# SNES_TST_Sheet1.net
KiCad netlist of a schematic drawn in Altium Designer
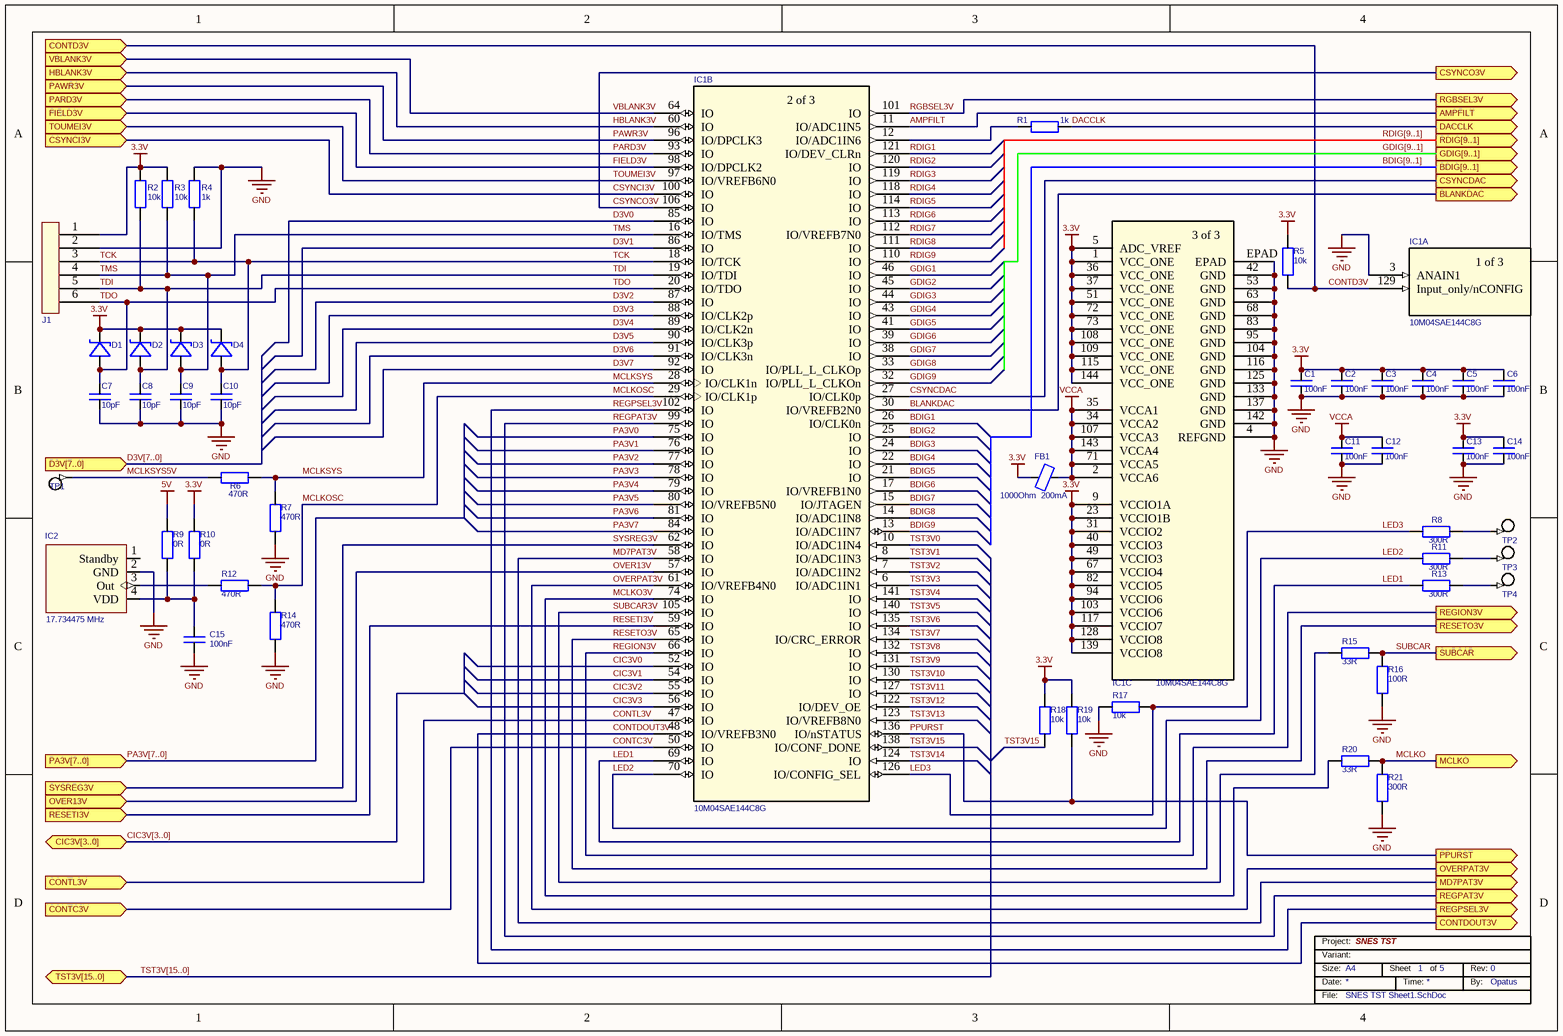
[diagram p0: SNES TST Sheet1.SchDoc]

(export (version "E")
  (design (tool "Eeschema 10.0.6"))
  (components
    (comp (ref "C1")
      (value "100nF")
      (footprint "Cap_0402_Chip")
      (fields
        (field (name "TOLERANCE") "±20%")
        (field (name "Comment") "Ceramic Capacitor 100nF 10V ±20% X7R 0402")
      )
      (libsource (lib "PCB") (part "Capacitor"))
    )
    (comp (ref "C2")
      (value "100nF")
      (footprint "Cap_0402_Chip")
      (fields
        (field (name "TOLERANCE") "±20%")
        (field (name "Comment") "Ceramic Capacitor 100nF 10V ±20% X7R 0402")
      )
      (libsource (lib "PCB") (part "Capacitor"))
    )
    (comp (ref "C3")
      (value "100nF")
      (footprint "Cap_0402_Chip")
      (fields
        (field (name "TOLERANCE") "±20%")
        (field (name "Comment") "Ceramic Capacitor 100nF 10V ±20% X7R 0402")
      )
      (libsource (lib "PCB") (part "Capacitor"))
    )
    (comp (ref "C4")
      (value "100nF")
      (footprint "Cap_0402_Chip")
      (fields
        (field (name "TOLERANCE") "±20%")
        (field (name "Comment") "Ceramic Capacitor 100nF 10V ±20% X7R 0402")
      )
      (libsource (lib "PCB") (part "Capacitor"))
    )
    (comp (ref "C5")
      (value "100nF")
      (footprint "Cap_0402_Chip")
      (fields
        (field (name "TOLERANCE") "±20%")
        (field (name "Comment") "Ceramic Capacitor 100nF 10V ±20% X7R 0402")
      )
      (libsource (lib "PCB") (part "Capacitor"))
    )
    (comp (ref "C6")
      (value "100nF")
      (footprint "Cap_0402_Chip")
      (fields
        (field (name "TOLERANCE") "±20%")
        (field (name "Comment") "Ceramic Capacitor 100nF 10V ±20% X7R 0402")
      )
      (libsource (lib "PCB") (part "Capacitor"))
    )
    (comp (ref "C7")
      (value "10pF")
      (footprint "Cap_0402_Chip")
      (fields
        (field (name "TOLERANCE") "±20%")
        (field (name "Comment") "Ceramic Capacitor 10pF 10V ±20% X7R 0402")
      )
      (libsource (lib "PCB") (part "Capacitor"))
    )
    (comp (ref "C8")
      (value "10pF")
      (footprint "Cap_0402_Chip")
      (fields
        (field (name "TOLERANCE") "±20%")
        (field (name "Comment") "Ceramic Capacitor 10pF 10V ±20% X7R 0402")
      )
      (libsource (lib "PCB") (part "Capacitor"))
    )
    (comp (ref "C9")
      (value "10pF")
      (footprint "Cap_0402_Chip")
      (fields
        (field (name "TOLERANCE") "±20%")
        (field (name "Comment") "Ceramic Capacitor 10pF 10V ±20% X7R 0402")
      )
      (libsource (lib "PCB") (part "Capacitor"))
    )
    (comp (ref "C10")
      (value "10pF")
      (footprint "Cap_0402_Chip")
      (fields
        (field (name "TOLERANCE") "±20%")
        (field (name "Comment") "Ceramic Capacitor 10pF 10V ±20% X7R 0402")
      )
      (libsource (lib "PCB") (part "Capacitor"))
    )
    (comp (ref "C11")
      (value "100nF")
      (footprint "Cap_0402_Chip")
      (fields
        (field (name "TOLERANCE") "±20%")
        (field (name "Comment") "Ceramic Capacitor 100nF 10V ±20% X7R 0402")
      )
      (libsource (lib "PCB") (part "Capacitor"))
    )
    (comp (ref "C12")
      (value "100nF")
      (footprint "Cap_0402_Chip")
      (fields
        (field (name "TOLERANCE") "±20%")
        (field (name "Comment") "Ceramic Capacitor 100nF 10V ±20% X7R 0402")
      )
      (libsource (lib "PCB") (part "Capacitor"))
    )
    (comp (ref "C13")
      (value "100nF")
      (footprint "Cap_0402_Chip")
      (fields
        (field (name "TOLERANCE") "±20%")
        (field (name "Comment") "Ceramic Capacitor 100nF 10V ±20% X7R 0402")
      )
      (libsource (lib "PCB") (part "Capacitor"))
    )
    (comp (ref "C14")
      (value "100nF")
      (footprint "Cap_0402_Chip")
      (fields
        (field (name "TOLERANCE") "±20%")
        (field (name "Comment") "Ceramic Capacitor 100nF 10V ±20% X7R 0402")
      )
      (libsource (lib "PCB") (part "Capacitor"))
    )
    (comp (ref "C15")
      (value "100nF")
      (footprint "Cap_0402_Chip")
      (fields
        (field (name "TOLERANCE") "±20%")
        (field (name "Comment") "Ceramic Capacitor 100nF 10V ±20% X7R 0402")
      )
      (libsource (lib "PCB") (part "Capacitor"))
    )
    (comp (ref "D1")
      (value "BAT54WS")
      (footprint "SOD323")
      (description "Schottky Diode")
      (fields (field (name "MANUFACTURER_PART_NUMBER") "BAT54WS-7-F"))
      (libsource (lib "PCB") (part "Schottky Diode"))
    )
    (comp (ref "D2")
      (value "BAT54WS")
      (footprint "SOD323")
      (description "Schottky Diode")
      (fields (field (name "MANUFACTURER_PART_NUMBER") "BAT54WS-7-F"))
      (libsource (lib "PCB") (part "Schottky Diode"))
    )
    (comp (ref "D3")
      (value "BAT54WS")
      (footprint "SOD323")
      (description "Schottky Diode")
      (fields (field (name "MANUFACTURER_PART_NUMBER") "BAT54WS-7-F"))
      (libsource (lib "PCB") (part "Schottky Diode"))
    )
    (comp (ref "D4")
      (value "BAT54WS")
      (footprint "SOD323")
      (description "Schottky Diode")
      (fields (field (name "MANUFACTURER_PART_NUMBER") "BAT54WS-7-F"))
      (libsource (lib "PCB") (part "Schottky Diode"))
    )
    (comp (ref "FB1")
      (value "1000Ohm  200mA")
      (footprint "Ind_0402_Chip")
      (fields (field (name "MANUFACTURER_PART_NUMBER") "MMZ1005S102CT000"))
      (libsource (lib "PCB") (part "Ferrite Bead"))
    )
    (comp (ref "IC1")
      (value "10M04SAE144C8G")
      (footprint "EQFP-144_A:1P65_")
      (description "No Description Available")
      (fields (field (name "COPYRIGHT") "Copyright (C) 2018 Accelerated Designs. All rights reserved"))
      (libsource (lib "") (part "10M08SAE144C8G_1"))
    )
    (comp (ref "IC2")
      (value "17.734475 MHz")
      (footprint "Quarz 7.5mm")
      (description "Oscillator")
      (fields
        (field (name "FREQUENCY") "17.734475 MHz")
        (field (name "MANUFACTURER_PART_NUMBER") "LFSPXO020648Bulk")
      )
      (libsource (lib "PCB") (part "Oscillator"))
    )
    (comp (ref "J1")
      (value "Conn 6P")
      (footprint "Con6P")
      (description "6 Pole Connector")
      (libsource (lib "PCB") (part "Conn 6P"))
    )
    (comp (ref "R1")
      (value "1k")
      (footprint "Res_0402_Chip")
      (fields (field (name "TOLERANCE") "±1%") (field (name "Comment") "Resistor 1k 0402 ±1%"))
      (libsource (lib "") (part "R_1"))
    )
    (comp (ref "R2")
      (value "10k")
      (footprint "Res_0402_Chip")
      (fields (field (name "TOLERANCE") "±1%") (field (name "Comment") "Resistor 10k 0402 ±1%"))
      (libsource (lib "") (part "R_2"))
    )
    (comp (ref "R3")
      (value "10k")
      (footprint "Res_0402_Chip")
      (fields (field (name "TOLERANCE") "±1%") (field (name "Comment") "Resistor 10k 0402 ±1%"))
      (libsource (lib "") (part "R_2"))
    )
    (comp (ref "R4")
      (value "1k")
      (footprint "Res_0402_Chip")
      (fields (field (name "TOLERANCE") "±1%") (field (name "Comment") "Resistor 1k 0402 ±1%"))
      (libsource (lib "") (part "R_3"))
    )
    (comp (ref "R5")
      (value "10k")
      (footprint "Res_0402_Chip")
      (fields (field (name "TOLERANCE") "±1%") (field (name "Comment") "Resistor 10k 0402 ±1%"))
      (libsource (lib "") (part "R_2"))
    )
    (comp (ref "R6")
      (value "470R")
      (footprint "Res_0603_Chip")
      (fields (field (name "TOLERANCE") "±1%") (field (name "Comment") "Resistor 470R 0603 ±1%"))
      (libsource (lib "PCB") (part "R"))
    )
    (comp (ref "R7")
      (value "470R")
      (footprint "Res_0603_Chip")
      (fields (field (name "TOLERANCE") "±1%") (field (name "Comment") "Resistor 470R 0603 ±1%"))
      (libsource (lib "") (part "R_2"))
    )
    (comp (ref "R8")
      (value "300R")
      (footprint "Res_0603_Chip")
      (fields (field (name "TOLERANCE") "±1%") (field (name "Comment") "Resistor 300R 0603 ±1%"))
      (libsource (lib "PCB") (part "R"))
    )
    (comp (ref "R9")
      (value "0R")
      (footprint "Res_0402_Chip")
      (fields (field (name "Comment") "Resistor 0R 0402 "))
      (libsource (lib "") (part "R_2"))
    )
    (comp (ref "R10")
      (value "0R")
      (footprint "Res_0402_Chip")
      (fields (field (name "Comment") "Resistor 0R 0402 "))
      (libsource (lib "") (part "R_2"))
    )
    (comp (ref "R11")
      (value "300R")
      (footprint "Res_0603_Chip")
      (fields (field (name "TOLERANCE") "±1%") (field (name "Comment") "Resistor 300R 0603 ±1%"))
      (libsource (lib "PCB") (part "R"))
    )
    (comp (ref "R12")
      (value "470R")
      (footprint "Res_0603_Chip")
      (fields (field (name "TOLERANCE") "±1%") (field (name "Comment") "Resistor 470R 0603 ±1%"))
      (libsource (lib "PCB") (part "R"))
    )
    (comp (ref "R13")
      (value "300R")
      (footprint "Res_0603_Chip")
      (fields (field (name "TOLERANCE") "±1%") (field (name "Comment") "Resistor 300R 0603 ±1%"))
      (libsource (lib "PCB") (part "R"))
    )
    (comp (ref "R14")
      (value "470R")
      (footprint "Res_0603_Chip")
      (fields (field (name "TOLERANCE") "±1%") (field (name "Comment") "Resistor 470R 0603 ±1%"))
      (libsource (lib "") (part "R_2"))
    )
    (comp (ref "R15")
      (value "33R")
      (footprint "Res_0603_Chip")
      (fields (field (name "TOLERANCE") "±1%") (field (name "Comment") "Resistor 33R 0603 ±1%"))
      (libsource (lib "PCB") (part "R"))
    )
    (comp (ref "R16")
      (value "100R")
      (footprint "Res_0603_Chip")
      (fields (field (name "TOLERANCE") "±1%") (field (name "Comment") "Resistor 100R 0603 ±1%"))
      (libsource (lib "") (part "R_2"))
    )
    (comp (ref "R17")
      (value "10k")
      (footprint "Res_0402_Chip")
      (fields (field (name "TOLERANCE") "±1%") (field (name "Comment") "Resistor 10k 0402 ±1%"))
      (libsource (lib "") (part "R_1"))
    )
    (comp (ref "R18")
      (value "10k")
      (footprint "Res_0402_Chip")
      (fields (field (name "TOLERANCE") "±1%") (field (name "Comment") "Resistor 10k 0402 ±1%"))
      (libsource (lib "") (part "R_2"))
    )
    (comp (ref "R19")
      (value "10k")
      (footprint "Res_0402_Chip")
      (fields (field (name "TOLERANCE") "±1%") (field (name "Comment") "Resistor 10k 0402 ±1%"))
      (libsource (lib "") (part "R_2"))
    )
    (comp (ref "R20")
      (value "33R")
      (footprint "Res_0603_Chip")
      (fields (field (name "TOLERANCE") "±1%") (field (name "Comment") "Resistor 33R 0603 ±1%"))
      (libsource (lib "PCB") (part "R"))
    )
    (comp (ref "R21")
      (value "300R")
      (footprint "Res_0603_Chip")
      (fields (field (name "TOLERANCE") "±1%") (field (name "Comment") "Resistor 300R 0603 ±1%"))
      (libsource (lib "") (part "R_2"))
    )
    (comp (ref "TP1")
      (value "Pin Connector")
      (footprint "Pin Connector Small")
      (libsource (lib "PCB") (part "Pin Connector"))
    )
    (comp (ref "TP2")
      (value "Pin Connector")
      (footprint "Pin Connector Small")
      (libsource (lib "PCB") (part "Pin Connector"))
    )
    (comp (ref "TP3")
      (value "Pin Connector")
      (footprint "Pin Connector Small")
      (libsource (lib "PCB") (part "Pin Connector"))
    )
    (comp (ref "TP4")
      (value "Pin Connector")
      (footprint "Pin Connector Small")
      (libsource (lib "PCB") (part "Pin Connector"))
    )
  )
  (nets
    (net (code "1") (name "/AMPFILT") (class "Default")
      (node (ref "IC1") (pin "11") (pinfunction "IO/ADC1IN5_11") (pintype "output"))
    )
    (net (code "2") (name "/BDIG1") (class "Default")
      (node (ref "IC1") (pin "26") (pinfunction "IO/CLK0n_26") (pintype "output"))
    )
    (net (code "3") (name "/BDIG2") (class "Default")
      (node (ref "IC1") (pin "25") (pinfunction "IO_25") (pintype "output"))
    )
    (net (code "4") (name "/BDIG3") (class "Default")
      (node (ref "IC1") (pin "24") (pinfunction "IO_24") (pintype "output"))
    )
    (net (code "5") (name "/BDIG4") (class "Default")
      (node (ref "IC1") (pin "22") (pinfunction "IO_22") (pintype "output"))
    )
    (net (code "6") (name "/BDIG5") (class "Default")
      (node (ref "IC1") (pin "21") (pinfunction "IO_21") (pintype "output"))
    )
    (net (code "7") (name "/BDIG6") (class "Default")
      (node (ref "IC1") (pin "17") (pinfunction "IO/VREFB1N0_17") (pintype "output"))
    )
    (net (code "8") (name "/BDIG7") (class "Default")
      (node (ref "IC1") (pin "15") (pinfunction "IO/JTAGEN_15") (pintype "output"))
    )
    (net (code "9") (name "/BDIG8") (class "Default")
      (node (ref "IC1") (pin "14") (pinfunction "IO/ADC1IN8_14") (pintype "output"))
    )
    (net (code "10") (name "/BDIG9") (class "Default")
      (node (ref "IC1") (pin "13") (pinfunction "IO/ADC1IN7_13") (pintype "bidirectional"))
    )
    (net (code "12") (name "/BLANKDAC") (class "Default")
      (node (ref "IC1") (pin "30") (pinfunction "IO/VREFB2N0_30") (pintype "output"))
    )
    (net (code "13") (name "/CIC3V0") (class "Default")
      (node (ref "IC1") (pin "52") (pinfunction "IO_52") (pintype "bidirectional"))
    )
    (net (code "14") (name "/CIC3V1") (class "Default")
      (node (ref "IC1") (pin "54") (pinfunction "IO_54") (pintype "bidirectional"))
    )
    (net (code "15") (name "/CIC3V2") (class "Default")
      (node (ref "IC1") (pin "55") (pinfunction "IO_55") (pintype "bidirectional"))
    )
    (net (code "16") (name "/CIC3V3") (class "Default")
      (node (ref "IC1") (pin "56") (pinfunction "IO_56") (pintype "bidirectional"))
    )
    (net (code "18") (name "/CONTC3V") (class "Default")
      (node (ref "IC1") (pin "50") (pinfunction "IO_50") (pintype "bidirectional"))
    )
    (net (code "19") (name "/CONTD3V") (class "Default")
      (node (ref "IC1") (pin "129") (pinfunction "Input_only/nCONFIG_129") (pintype "input"))
      (node (ref "R5") (pin "2") (pintype "passive"))
    )
    (net (code "20") (name "/CONTDOUT3V") (class "Default")
      (node (ref "IC1") (pin "48") (pinfunction "IO/VREFB3N0_48") (pintype "bidirectional"))
    )
    (net (code "21") (name "/CONTL3V") (class "Default")
      (node (ref "IC1") (pin "47") (pinfunction "IO_47") (pintype "bidirectional"))
    )
    (net (code "22") (name "/CSYNCDAC") (class "Default")
      (node (ref "IC1") (pin "27") (pinfunction "IO/CLK0p_27") (pintype "output"))
    )
    (net (code "23") (name "/CSYNCI3V") (class "Default")
      (node (ref "IC1") (pin "100") (pinfunction "IO_100") (pintype "bidirectional"))
    )
    (net (code "24") (name "/CSYNCO3V") (class "Default")
      (node (ref "IC1") (pin "106") (pinfunction "IO_106") (pintype "bidirectional"))
    )
    (net (code "25") (name "/D3V0") (class "Default")
      (node (ref "IC1") (pin "85") (pinfunction "IO_85") (pintype "bidirectional"))
    )
    (net (code "26") (name "/D3V1") (class "Default")
      (node (ref "IC1") (pin "86") (pinfunction "IO_86") (pintype "bidirectional"))
    )
    (net (code "27") (name "/D3V2") (class "Default")
      (node (ref "IC1") (pin "87") (pinfunction "IO_87") (pintype "bidirectional"))
    )
    (net (code "28") (name "/D3V3") (class "Default")
      (node (ref "IC1") (pin "88") (pinfunction "IO/CLK2p_88") (pintype "bidirectional"))
    )
    (net (code "29") (name "/D3V4") (class "Default")
      (node (ref "IC1") (pin "89") (pinfunction "IO/CLK2n_89") (pintype "bidirectional"))
    )
    (net (code "30") (name "/D3V5") (class "Default")
      (node (ref "IC1") (pin "90") (pinfunction "IO/CLK3p_90") (pintype "bidirectional"))
    )
    (net (code "31") (name "/D3V6") (class "Default")
      (node (ref "IC1") (pin "91") (pinfunction "IO/CLK3n_91") (pintype "bidirectional"))
    )
    (net (code "32") (name "/D3V7") (class "Default")
      (node (ref "IC1") (pin "92") (pinfunction "IO_92") (pintype "bidirectional"))
    )
    (net (code "34") (name "/DACCLK") (class "Default") (node (ref "R1") (pin "2") (pintype "passive")))
    (net (code "35") (name "/FIELD3V") (class "Default")
      (node (ref "IC1") (pin "98") (pinfunction "IO/DPCLK2_98") (pintype "bidirectional"))
    )
    (net (code "36") (name "/GDIG1") (class "Default")
      (node (ref "IC1") (pin "46") (pinfunction "IO_46") (pintype "output"))
    )
    (net (code "37") (name "/GDIG2") (class "Default")
      (node (ref "IC1") (pin "45") (pinfunction "IO_45") (pintype "output"))
    )
    (net (code "38") (name "/GDIG3") (class "Default")
      (node (ref "IC1") (pin "44") (pinfunction "IO_44") (pintype "output"))
    )
    (net (code "39") (name "/GDIG4") (class "Default")
      (node (ref "IC1") (pin "43") (pinfunction "IO_43") (pintype "output"))
    )
    (net (code "40") (name "/GDIG5") (class "Default")
      (node (ref "IC1") (pin "41") (pinfunction "IO_41") (pintype "output"))
    )
    (net (code "41") (name "/GDIG6") (class "Default")
      (node (ref "IC1") (pin "39") (pinfunction "IO_39") (pintype "output"))
    )
    (net (code "42") (name "/GDIG7") (class "Default")
      (node (ref "IC1") (pin "38") (pinfunction "IO_38") (pintype "output"))
    )
    (net (code "43") (name "/GDIG8") (class "Default")
      (node (ref "IC1") (pin "33") (pinfunction "IO/PLL_L_CLKOp_33") (pintype "output"))
    )
    (net (code "44") (name "/GDIG9") (class "Default")
      (node (ref "IC1") (pin "32") (pinfunction "IO/PLL_L_CLKOn_32") (pintype "output"))
    )
    (net (code "46") (name "/HBLANK3V") (class "Default")
      (node (ref "IC1") (pin "60") (pinfunction "IO_60") (pintype "bidirectional"))
    )
    (net (code "47") (name "/LED1") (class "Default")
      (node (ref "IC1") (pin "69") (pinfunction "IO_69") (pintype "bidirectional"))
      (node (ref "R13") (pin "2") (pintype "passive"))
    )
    (net (code "48") (name "/LED2") (class "Default")
      (node (ref "IC1") (pin "70") (pinfunction "IO_70") (pintype "bidirectional"))
      (node (ref "R11") (pin "2") (pintype "passive"))
    )
    (net (code "49") (name "/LED3") (class "Default")
      (node (ref "IC1") (pin "126") (pinfunction "IO/CONFIG_SEL_126") (pintype "bidirectional"))
      (node (ref "R17") (pin "2") (pintype "passive"))
      (node (ref "R8") (pin "2") (pintype "passive"))
    )
    (net (code "50") (name "/MCLKO") (class "Default")
      (node (ref "R20") (pin "1") (pintype "passive"))
      (node (ref "R21") (pin "1") (pintype "passive"))
    )
    (net (code "51") (name "/MCLKO3V") (class "Default")
      (node (ref "IC1") (pin "74") (pinfunction "IO_74") (pintype "bidirectional"))
      (node (ref "R20") (pin "2") (pintype "passive"))
    )
    (net (code "52") (name "/MCLKOSC") (class "Default")
      (node (ref "IC1") (pin "29") (pinfunction "IO/CLK1p_29") (pintype "bidirectional"))
      (node (ref "R12") (pin "1") (pintype "passive"))
      (node (ref "R14") (pin "1") (pintype "passive"))
    )
    (net (code "53") (name "/MCLKSYS") (class "Default")
      (node (ref "IC1") (pin "28") (pinfunction "IO/CLK1n_28") (pintype "bidirectional"))
      (node (ref "R6") (pin "1") (pintype "passive"))
      (node (ref "R7") (pin "1") (pintype "passive"))
    )
    (net (code "54") (name "/MCLKSYS5V") (class "Default")
      (node (ref "R6") (pin "2") (pintype "passive"))
      (node (ref "TP1") (pin "1") (pinfunction "0_1") (pintype "output"))
    )
    (net (code "55") (name "/MD7PAT3V") (class "Default")
      (node (ref "IC1") (pin "58") (pinfunction "IO_58") (pintype "bidirectional"))
    )
    (net (code "56") (name "/OVER13V") (class "Default")
      (node (ref "IC1") (pin "57") (pinfunction "IO_57") (pintype "bidirectional"))
    )
    (net (code "57") (name "/OVERPAT3V") (class "Default")
      (node (ref "IC1") (pin "61") (pinfunction "IO/VREFB4N0_61") (pintype "bidirectional"))
    )
    (net (code "58") (name "/PA3V0") (class "Default")
      (node (ref "IC1") (pin "75") (pinfunction "IO_75") (pintype "bidirectional"))
    )
    (net (code "59") (name "/PA3V1") (class "Default")
      (node (ref "IC1") (pin "76") (pinfunction "IO_76") (pintype "bidirectional"))
    )
    (net (code "60") (name "/PA3V2") (class "Default")
      (node (ref "IC1") (pin "77") (pinfunction "IO_77") (pintype "bidirectional"))
    )
    (net (code "61") (name "/PA3V3") (class "Default")
      (node (ref "IC1") (pin "78") (pinfunction "IO_78") (pintype "bidirectional"))
    )
    (net (code "62") (name "/PA3V4") (class "Default")
      (node (ref "IC1") (pin "79") (pinfunction "IO_79") (pintype "bidirectional"))
    )
    (net (code "63") (name "/PA3V5") (class "Default")
      (node (ref "IC1") (pin "80") (pinfunction "IO/VREFB5N0_80") (pintype "bidirectional"))
    )
    (net (code "64") (name "/PA3V6") (class "Default")
      (node (ref "IC1") (pin "81") (pinfunction "IO_81") (pintype "bidirectional"))
    )
    (net (code "65") (name "/PA3V7") (class "Default")
      (node (ref "IC1") (pin "84") (pinfunction "IO_84") (pintype "bidirectional"))
    )
    (net (code "67") (name "/PARD3V") (class "Default")
      (node (ref "IC1") (pin "93") (pinfunction "IO_93") (pintype "bidirectional"))
    )
    (net (code "68") (name "/PAWR3V") (class "Default")
      (node (ref "IC1") (pin "96") (pinfunction "IO/DPCLK3_96") (pintype "bidirectional"))
    )
    (net (code "69") (name "/PPURST") (class "Default")
      (node (ref "IC1") (pin "136") (pinfunction "IO/nSTATUS_136") (pintype "bidirectional"))
      (node (ref "R19") (pin "2") (pintype "passive"))
    )
    (net (code "70") (name "/RDIG1") (class "Default")
      (node (ref "IC1") (pin "121") (pinfunction "IO/DEV_CLRn_121") (pintype "output"))
    )
    (net (code "71") (name "/RDIG2") (class "Default")
      (node (ref "IC1") (pin "120") (pinfunction "IO_120") (pintype "output"))
    )
    (net (code "72") (name "/RDIG3") (class "Default")
      (node (ref "IC1") (pin "119") (pinfunction "IO_119") (pintype "output"))
    )
    (net (code "73") (name "/RDIG4") (class "Default")
      (node (ref "IC1") (pin "118") (pinfunction "IO_118") (pintype "output"))
    )
    (net (code "74") (name "/RDIG5") (class "Default")
      (node (ref "IC1") (pin "114") (pinfunction "IO_114") (pintype "output"))
    )
    (net (code "75") (name "/RDIG6") (class "Default")
      (node (ref "IC1") (pin "113") (pinfunction "IO_113") (pintype "output"))
    )
    (net (code "76") (name "/RDIG7") (class "Default")
      (node (ref "IC1") (pin "112") (pinfunction "IO/VREFB7N0_112") (pintype "output"))
    )
    (net (code "77") (name "/RDIG8") (class "Default")
      (node (ref "IC1") (pin "111") (pinfunction "IO_111") (pintype "output"))
    )
    (net (code "78") (name "/RDIG9") (class "Default")
      (node (ref "IC1") (pin "110") (pinfunction "IO_110") (pintype "output"))
    )
    (net (code "80") (name "/REGION3V") (class "Default")
      (node (ref "IC1") (pin "66") (pinfunction "IO_66") (pintype "bidirectional"))
    )
    (net (code "81") (name "/REGPAT3V") (class "Default")
      (node (ref "IC1") (pin "99") (pinfunction "IO_99") (pintype "bidirectional"))
    )
    (net (code "82") (name "/REGPSEL3V") (class "Default")
      (node (ref "IC1") (pin "102") (pinfunction "IO_102") (pintype "bidirectional"))
    )
    (net (code "83") (name "/RESETI3V") (class "Default")
      (node (ref "IC1") (pin "59") (pinfunction "IO_59") (pintype "bidirectional"))
    )
    (net (code "84") (name "/RESETO3V") (class "Default")
      (node (ref "IC1") (pin "65") (pinfunction "IO_65") (pintype "bidirectional"))
    )
    (net (code "85") (name "/RGBSEL3V") (class "Default")
      (node (ref "IC1") (pin "101") (pinfunction "IO_101") (pintype "output"))
    )
    (net (code "86") (name "/SUBCAR") (class "Default")
      (node (ref "R15") (pin "1") (pintype "passive"))
      (node (ref "R16") (pin "1") (pintype "passive"))
    )
    (net (code "87") (name "/SUBCAR3V") (class "Default")
      (node (ref "IC1") (pin "105") (pinfunction "IO_105") (pintype "bidirectional"))
      (node (ref "R15") (pin "2") (pintype "passive"))
    )
    (net (code "88") (name "/SYSREG3V") (class "Default")
      (node (ref "IC1") (pin "62") (pinfunction "IO_62") (pintype "bidirectional"))
    )
    (net (code "89") (name "/TCK") (class "Default")
      (node (ref "C10") (pin "1") (pintype "passive"))
      (node (ref "D4") (pin "2") (pinfunction "A_2") (pintype "passive"))
      (node (ref "IC1") (pin "18") (pinfunction "IO/TCK_18") (pintype "bidirectional"))
      (node (ref "J1") (pin "3") (pintype "passive"))
      (node (ref "R4") (pin "1") (pintype "passive"))
    )
    (net (code "90") (name "/TDI") (class "Default")
      (node (ref "C8") (pin "1") (pintype "passive"))
      (node (ref "D2") (pin "2") (pinfunction "A_2") (pintype "passive"))
      (node (ref "IC1") (pin "19") (pinfunction "IO/TDI_19") (pintype "bidirectional"))
      (node (ref "J1") (pin "5") (pintype "passive"))
      (node (ref "R2") (pin "2") (pintype "passive"))
    )
    (net (code "91") (name "/TDO") (class "Default")
      (node (ref "C7") (pin "1") (pintype "passive"))
      (node (ref "D1") (pin "2") (pinfunction "A_2") (pintype "passive"))
      (node (ref "IC1") (pin "20") (pinfunction "IO/TDO_20") (pintype "bidirectional"))
      (node (ref "J1") (pin "6") (pintype "passive"))
    )
    (net (code "92") (name "/TMS") (class "Default")
      (node (ref "C9") (pin "1") (pintype "passive"))
      (node (ref "D3") (pin "2") (pinfunction "A_2") (pintype "passive"))
      (node (ref "IC1") (pin "16") (pinfunction "IO/TMS_16") (pintype "bidirectional"))
      (node (ref "J1") (pin "4") (pintype "passive"))
      (node (ref "R3") (pin "2") (pintype "passive"))
    )
    (net (code "93") (name "/TOUMEI3V") (class "Default")
      (node (ref "IC1") (pin "97") (pinfunction "IO/VREFB6N0_97") (pintype "bidirectional"))
    )
    (net (code "94") (name "/TST3V0") (class "Default")
      (node (ref "IC1") (pin "10") (pinfunction "IO/ADC1IN4_10") (pintype "input"))
    )
    (net (code "95") (name "/TST3V1") (class "Default")
      (node (ref "IC1") (pin "8") (pinfunction "IO/ADC1IN3_8") (pintype "input"))
    )
    (net (code "96") (name "/TST3V2") (class "Default")
      (node (ref "IC1") (pin "7") (pinfunction "IO/ADC1IN2_7") (pintype "input"))
    )
    (net (code "97") (name "/TST3V3") (class "Default")
      (node (ref "IC1") (pin "6") (pinfunction "IO/ADC1IN1_6") (pintype "input"))
    )
    (net (code "98") (name "/TST3V4") (class "Default")
      (node (ref "IC1") (pin "141") (pinfunction "IO_141") (pintype "input"))
    )
    (net (code "99") (name "/TST3V5") (class "Default")
      (node (ref "IC1") (pin "140") (pinfunction "IO_140") (pintype "input"))
    )
    (net (code "100") (name "/TST3V6") (class "Default")
      (node (ref "IC1") (pin "135") (pinfunction "IO_135") (pintype "input"))
    )
    (net (code "101") (name "/TST3V7") (class "Default")
      (node (ref "IC1") (pin "134") (pinfunction "IO/CRC_ERROR_134") (pintype "input"))
    )
    (net (code "102") (name "/TST3V8") (class "Default")
      (node (ref "IC1") (pin "132") (pinfunction "IO_132") (pintype "input"))
    )
    (net (code "103") (name "/TST3V9") (class "Default")
      (node (ref "IC1") (pin "131") (pinfunction "IO_131") (pintype "input"))
    )
    (net (code "104") (name "/TST3V10") (class "Default")
      (node (ref "IC1") (pin "130") (pinfunction "IO_130") (pintype "input"))
    )
    (net (code "105") (name "/TST3V11") (class "Default")
      (node (ref "IC1") (pin "127") (pinfunction "IO_127") (pintype "input"))
    )
    (net (code "106") (name "/TST3V12") (class "Default")
      (node (ref "IC1") (pin "122") (pinfunction "IO/DEV_OE_122") (pintype "input"))
    )
    (net (code "107") (name "/TST3V13") (class "Default")
      (node (ref "IC1") (pin "123") (pinfunction "IO/VREFB8N0_123") (pintype "input"))
    )
    (net (code "108") (name "/TST3V14") (class "Default")
      (node (ref "IC1") (pin "124") (pinfunction "IO_124") (pintype "input"))
    )
    (net (code "109") (name "/TST3V15") (class "Default")
      (node (ref "IC1") (pin "138") (pinfunction "IO/CONF_DONE_138") (pintype "bidirectional"))
      (node (ref "R18") (pin "2") (pintype "passive"))
    )
    (net (code "111") (name "/VBLANK3V") (class "Default")
      (node (ref "IC1") (pin "64") (pinfunction "IO_64") (pintype "bidirectional"))
    )
    (net (code "112") (name "3.3V") (class "Default")
      (node (ref "C1") (pin "1") (pintype "passive"))
      (node (ref "C13") (pin "1") (pintype "passive"))
      (node (ref "C14") (pin "1") (pintype "passive"))
      (node (ref "C2") (pin "1") (pintype "passive"))
      (node (ref "C3") (pin "1") (pintype "passive"))
      (node (ref "C4") (pin "1") (pintype "passive"))
      (node (ref "C5") (pin "1") (pintype "passive"))
      (node (ref "C6") (pin "1") (pintype "passive"))
      (node (ref "D1") (pin "1") (pinfunction "K_1") (pintype "passive"))
      (node (ref "D2") (pin "1") (pinfunction "K_1") (pintype "passive"))
      (node (ref "D3") (pin "1") (pinfunction "K_1") (pintype "passive"))
      (node (ref "D4") (pin "1") (pinfunction "K_1") (pintype "passive"))
      (node (ref "FB1") (pin "1") (pintype "passive"))
      (node (ref "IC1") (pin "1") (pinfunction "VCC_ONE_1") (pintype "power_in"))
      (node (ref "IC1") (pin "103") (pinfunction "VCCIO6_103") (pintype "power_in"))
      (node (ref "IC1") (pin "108") (pinfunction "VCC_ONE_108") (pintype "power_in"))
      (node (ref "IC1") (pin "109") (pinfunction "VCC_ONE_109") (pintype "power_in"))
      (node (ref "IC1") (pin "115") (pinfunction "VCC_ONE_115") (pintype "power_in"))
      (node (ref "IC1") (pin "117") (pinfunction "VCCIO7_117") (pintype "power_in"))
      (node (ref "IC1") (pin "128") (pinfunction "VCCIO8_128") (pintype "power_in"))
      (node (ref "IC1") (pin "139") (pinfunction "VCCIO8_139") (pintype "power_in"))
      (node (ref "IC1") (pin "144") (pinfunction "VCC_ONE_144") (pintype "power_in"))
      (node (ref "IC1") (pin "23") (pinfunction "VCCIO1B_23") (pintype "power_in"))
      (node (ref "IC1") (pin "31") (pinfunction "VCCIO2_31") (pintype "power_in"))
      (node (ref "IC1") (pin "36") (pinfunction "VCC_ONE_36") (pintype "power_in"))
      (node (ref "IC1") (pin "37") (pinfunction "VCC_ONE_37") (pintype "power_in"))
      (node (ref "IC1") (pin "40") (pinfunction "VCCIO3_40") (pintype "power_in"))
      (node (ref "IC1") (pin "49") (pinfunction "VCCIO3_49") (pintype "power_in"))
      (node (ref "IC1") (pin "5") (pinfunction "ADC_VREF_5") (pintype "power_in"))
      (node (ref "IC1") (pin "51") (pinfunction "VCC_ONE_51") (pintype "power_in"))
      (node (ref "IC1") (pin "67") (pinfunction "VCCIO4_67") (pintype "power_in"))
      (node (ref "IC1") (pin "72") (pinfunction "VCC_ONE_72") (pintype "power_in"))
      (node (ref "IC1") (pin "73") (pinfunction "VCC_ONE_73") (pintype "power_in"))
      (node (ref "IC1") (pin "82") (pinfunction "VCCIO5_82") (pintype "power_in"))
      (node (ref "IC1") (pin "9") (pinfunction "VCCIO1A_9") (pintype "power_in"))
      (node (ref "IC1") (pin "94") (pinfunction "VCCIO6_94") (pintype "power_in"))
      (node (ref "J1") (pin "1") (pintype "passive"))
      (node (ref "R10") (pin "1") (pintype "passive"))
      (node (ref "R18") (pin "1") (pintype "passive"))
      (node (ref "R19") (pin "1") (pintype "passive"))
      (node (ref "R2") (pin "1") (pintype "passive"))
      (node (ref "R3") (pin "1") (pintype "passive"))
      (node (ref "R5") (pin "1") (pintype "passive"))
    )
    (net (code "113") (name "5V") (class "Default") (node (ref "R9") (pin "1") (pintype "passive")))
    (net (code "114") (name "GND") (class "Default")
      (node (ref "C1") (pin "2") (pintype "passive"))
      (node (ref "C10") (pin "2") (pintype "passive"))
      (node (ref "C11") (pin "2") (pintype "passive"))
      (node (ref "C12") (pin "2") (pintype "passive"))
      (node (ref "C13") (pin "2") (pintype "passive"))
      (node (ref "C14") (pin "2") (pintype "passive"))
      (node (ref "C15") (pin "2") (pintype "passive"))
      (node (ref "C2") (pin "2") (pintype "passive"))
      (node (ref "C3") (pin "2") (pintype "passive"))
      (node (ref "C4") (pin "2") (pintype "passive"))
      (node (ref "C5") (pin "2") (pintype "passive"))
      (node (ref "C6") (pin "2") (pintype "passive"))
      (node (ref "C7") (pin "2") (pintype "passive"))
      (node (ref "C8") (pin "2") (pintype "passive"))
      (node (ref "C9") (pin "2") (pintype "passive"))
      (node (ref "IC1") (pin "104") (pinfunction "GND_104") (pintype "power_in"))
      (node (ref "IC1") (pin "116") (pinfunction "GND_116") (pintype "power_in"))
      (node (ref "IC1") (pin "125") (pinfunction "GND_125") (pintype "power_in"))
      (node (ref "IC1") (pin "133") (pinfunction "GND_133") (pintype "power_in"))
      (node (ref "IC1") (pin "137") (pinfunction "GND_137") (pintype "power_in"))
      (node (ref "IC1") (pin "142") (pinfunction "GND_142") (pintype "power_in"))
      (node (ref "IC1") (pin "3") (pinfunction "ANAIN1_3") (pintype "input"))
      (node (ref "IC1") (pin "4") (pinfunction "REFGND_4") (pintype "power_in"))
      (node (ref "IC1") (pin "42") (pinfunction "GND_42") (pintype "power_in"))
      (node (ref "IC1") (pin "53") (pinfunction "GND_53") (pintype "power_in"))
      (node (ref "IC1") (pin "63") (pinfunction "GND_63") (pintype "power_in"))
      (node (ref "IC1") (pin "68") (pinfunction "GND_68") (pintype "power_in"))
      (node (ref "IC1") (pin "83") (pinfunction "GND_83") (pintype "power_in"))
      (node (ref "IC1") (pin "95") (pinfunction "GND_95") (pintype "power_in"))
      (node (ref "IC1") (pin "EPAD") (pinfunction "EPAD_EPAD") (pintype "power_in"))
      (node (ref "IC2") (pin "2") (pinfunction "GND_2") (pintype "power_in"))
      (node (ref "J1") (pin "2") (pintype "passive"))
      (node (ref "R14") (pin "2") (pintype "passive"))
      (node (ref "R16") (pin "2") (pintype "passive"))
      (node (ref "R17") (pin "1") (pintype "passive"))
      (node (ref "R21") (pin "2") (pintype "passive"))
      (node (ref "R4") (pin "2") (pintype "passive"))
      (node (ref "R7") (pin "2") (pintype "passive"))
    )
    (net (code "115") (name "Net-(IC1B-IO{slash}ADC1IN6)") (class "Default")
      (node (ref "IC1") (pin "12") (pinfunction "IO/ADC1IN6_12") (pintype "output"))
      (node (ref "R1") (pin "1") (pintype "passive"))
    )
    (net (code "116") (name "Net-(IC2-Out)") (class "Default")
      (node (ref "IC2") (pin "3") (pinfunction "Out_3") (pintype "output"))
      (node (ref "R12") (pin "2") (pintype "passive"))
    )
    (net (code "117") (name "Net-(IC2-VDD)") (class "Default")
      (node (ref "C15") (pin "1") (pintype "passive"))
      (node (ref "IC2") (pin "4") (pinfunction "VDD_4") (pintype "power_in"))
      (node (ref "R10") (pin "2") (pintype "passive"))
      (node (ref "R9") (pin "2") (pintype "passive"))
    )
    (net (code "118") (name "Net-(TP2-0)") (class "Default")
      (node (ref "R8") (pin "1") (pintype "passive"))
      (node (ref "TP2") (pin "1") (pinfunction "0_1") (pintype "output"))
    )
    (net (code "119") (name "Net-(TP3-0)") (class "Default")
      (node (ref "R11") (pin "1") (pintype "passive"))
      (node (ref "TP3") (pin "1") (pinfunction "0_1") (pintype "output"))
    )
    (net (code "120") (name "Net-(TP4-0)") (class "Default")
      (node (ref "R13") (pin "1") (pintype "passive"))
      (node (ref "TP4") (pin "1") (pinfunction "0_1") (pintype "output"))
    )
    (net (code "121") (name "VCCA") (class "Default")
      (node (ref "C11") (pin "1") (pintype "passive"))
      (node (ref "C12") (pin "1") (pintype "passive"))
      (node (ref "FB1") (pin "2") (pintype "passive"))
      (node (ref "IC1") (pin "107") (pinfunction "VCCA3_107") (pintype "power_in"))
      (node (ref "IC1") (pin "143") (pinfunction "VCCA4_143") (pintype "power_in"))
      (node (ref "IC1") (pin "2") (pinfunction "VCCA6_2") (pintype "power_in"))
      (node (ref "IC1") (pin "34") (pinfunction "VCCA2_34") (pintype "power_in"))
      (node (ref "IC1") (pin "35") (pinfunction "VCCA1_35") (pintype "power_in"))
      (node (ref "IC1") (pin "71") (pinfunction "VCCA5_71") (pintype "power_in"))
    )
    (net (code "122") (name "unconnected-(IC2-Standby-Pad1)") (class "Default")
      (node (ref "IC2") (pin "1") (pinfunction "Standby_1") (pintype "passive"))
    )
  )
)
